# I2C_Header.net
KiCad netlist of a schematic drawn in Altium Designer
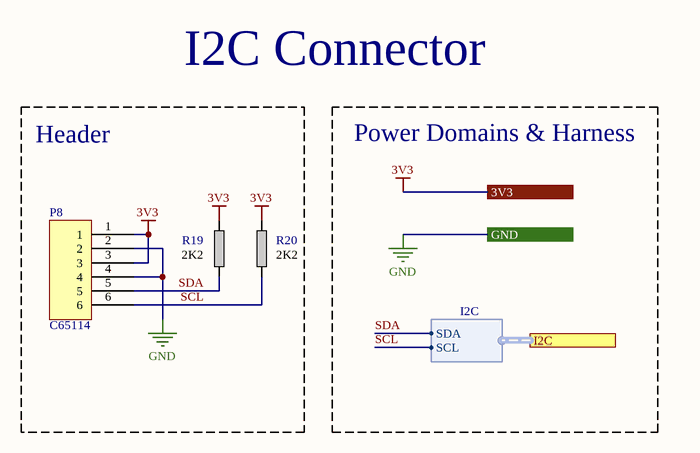
[diagram p0: I2C_Header.SchDoc]

(export (version "E")
  (design (tool "Eeschema 10.0.6"))
  (components
    (comp (ref "P8")
      (value "HEADER 6POS")
      (footprint "HEADER 3X2")
      (description "Straight 2 6 2.54mm Black Straight,P=2.54mm  Pin Headers ROHS")
      (fields
        (field (name "MANUFACTURER") "BOOMELE(Boom Precision Elec)")
        (field (name "MANUFACTURER PART NUMBER") "C65114")
      )
      (libsource (lib "Library") (part "HEADER 6POS"))
    )
    (comp (ref "R19")
      (value "2K2")
      (footprint "0805")
      (description "125mW Thick Film Resistors ±5% 2.2kΩ 0805  Chip Resistor - Surface Mount ROHS")
      (fields
        (field (name "MANUFACTURER") "LIZ Elec")
        (field (name "MANUFACTURER PART NUMBER") "CR0805J80222G")
      )
      (libsource (lib "Library") (part "RES"))
    )
    (comp (ref "R20")
      (value "2K2")
      (footprint "0805")
      (description "125mW Thick Film Resistors ±5% 2.2kΩ 0805  Chip Resistor - Surface Mount ROHS")
      (fields
        (field (name "MANUFACTURER") "LIZ Elec")
        (field (name "MANUFACTURER PART NUMBER") "CR0805J80222G")
      )
      (libsource (lib "Library") (part "RES"))
    )
  )
  (nets
    (net (code "2") (name "/SCL") (class "Default")
      (node (ref "P8") (pin "6") (pinfunction "6_6") (pintype "passive"))
      (node (ref "R20") (pin "2") (pinfunction "2_2") (pintype "passive"))
    )
    (net (code "3") (name "/SDA") (class "Default")
      (node (ref "P8") (pin "5") (pinfunction "5_5") (pintype "passive"))
      (node (ref "R19") (pin "2") (pinfunction "2_2") (pintype "passive"))
    )
    (net (code "5") (name "3V3") (class "Default")
      (node (ref "P8") (pin "1") (pinfunction "1_1") (pintype "passive"))
      (node (ref "P8") (pin "3") (pinfunction "3_3") (pintype "passive"))
      (node (ref "R19") (pin "1") (pinfunction "1_1") (pintype "passive"))
      (node (ref "R20") (pin "1") (pinfunction "1_1") (pintype "passive"))
    )
    (net (code "6") (name "GND") (class "Default")
      (node (ref "P8") (pin "2") (pinfunction "2_2") (pintype "passive"))
      (node (ref "P8") (pin "4") (pinfunction "4_4") (pintype "passive"))
    )
  )
)
